# 10_1a.net
KiCad netlist of a schematic drawn in EasyEDA
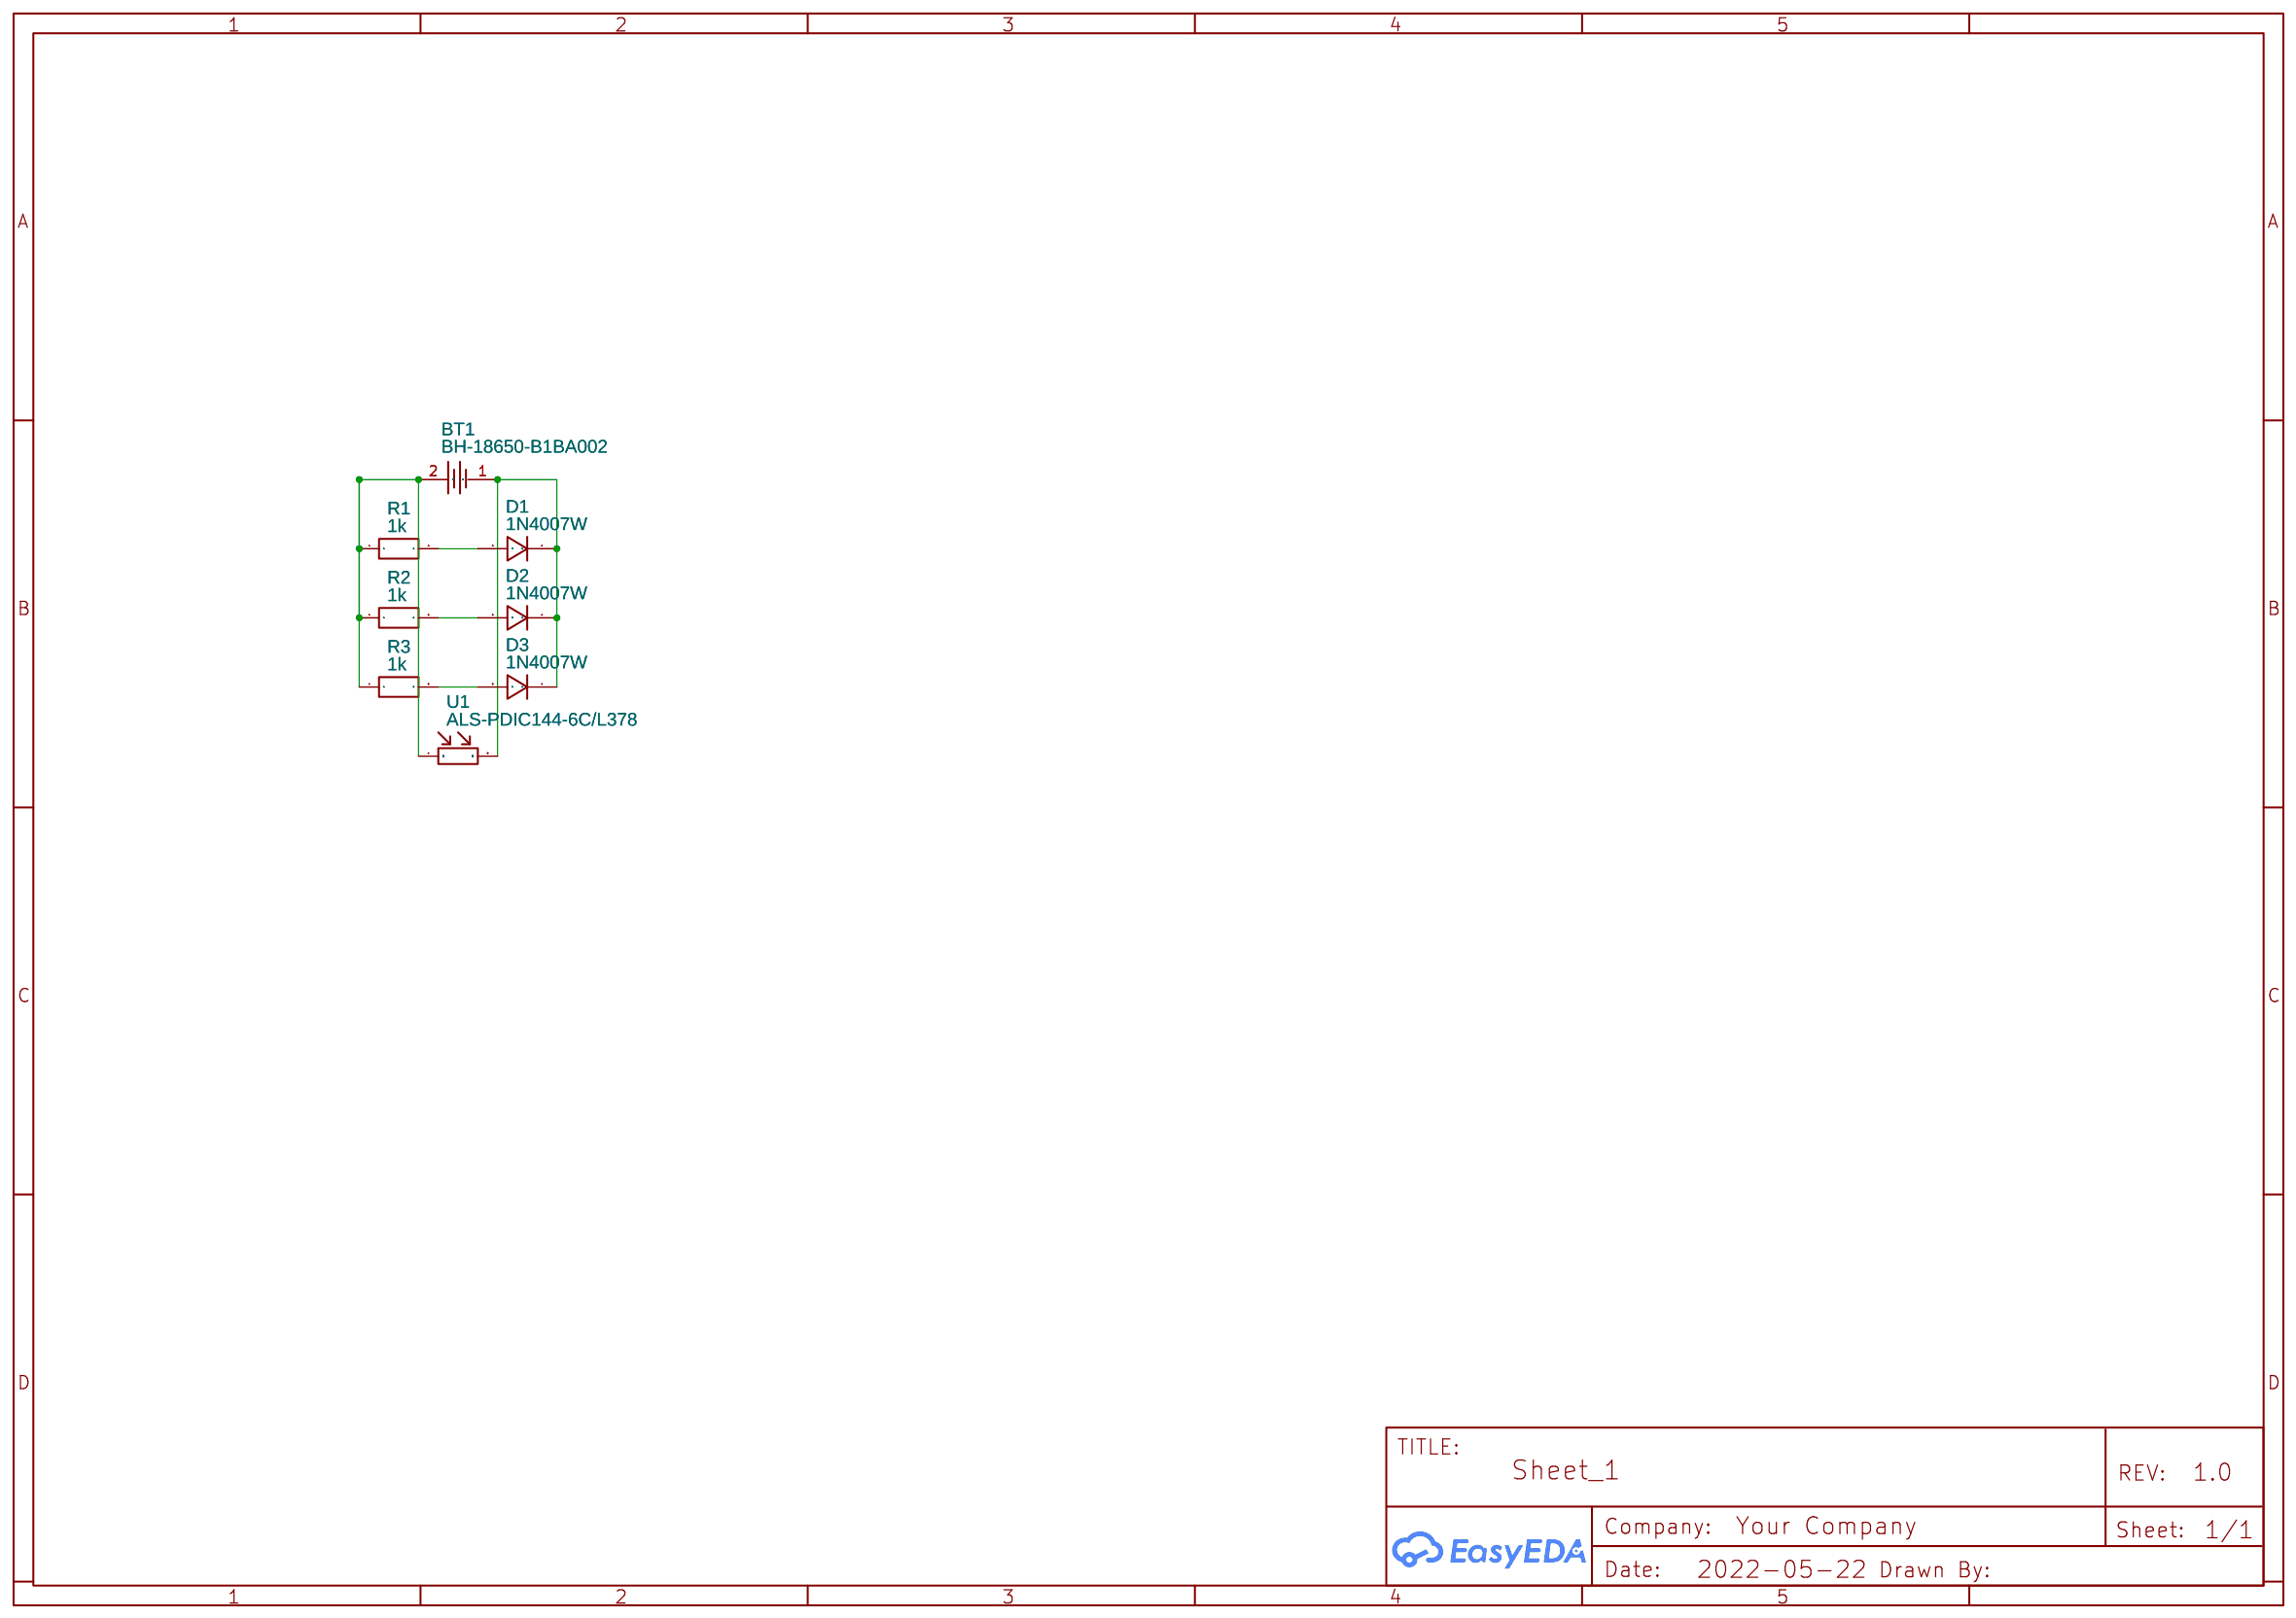
[diagram p0: schematic sheet]

(export (version "E")
  (design (tool "Eeschema 10.0.6"))
  (components
    (comp (ref "BT1")
      (value "BH-18650-B1BA002")
      (fields (field (name "BOM_Supplier Part") "C2988620"))
      (libsource (lib "") (part "BH-18650-B1BA002"))
    )
    (comp (ref "D1")
      (value "1N4007W")
      (fields (field (name "BOM_Supplier Part") "C328592"))
      (libsource (lib "") (part "1N4007W"))
    )
    (comp (ref "D2")
      (value "1N4007W")
      (fields (field (name "BOM_Supplier Part") "C328592"))
      (libsource (lib "") (part "1N4007W"))
    )
    (comp (ref "D3")
      (value "1N4007W")
      (fields (field (name "BOM_Supplier Part") "C328592"))
      (libsource (lib "") (part "1N4007W"))
    )
    (comp (ref "R1") (value "1k") (libsource (lib "") (part "R_0603_EU")))
    (comp (ref "R2") (value "1k") (libsource (lib "") (part "R_0603_EU")))
    (comp (ref "R3") (value "1k") (libsource (lib "") (part "R_0603_EU")))
    (comp (ref "U1")
      (value "ALS-PDIC144-6C/L378")
      (fields (field (name "BOM_Supplier Part") "C2943463"))
      (libsource (lib "") (part "ALS-PDIC144-6C/L378"))
    )
  )
  (nets
    (net (code "1") (name "Net-(D1-Pad2)") (class "Default")
      (node (ref "D1") (pin "2") (pinfunction "2_2") (pintype "unspecified"))
      (node (ref "R1") (pin "2") (pinfunction "2_2") (pintype "unspecified"))
    )
    (net (code "2") (name "Net-(D2-Pad2)") (class "Default")
      (node (ref "D2") (pin "2") (pinfunction "2_2") (pintype "unspecified"))
      (node (ref "R2") (pin "2") (pinfunction "2_2") (pintype "unspecified"))
    )
    (net (code "3") (name "Net-(D3-Pad2)") (class "Default")
      (node (ref "D3") (pin "2") (pinfunction "2_2") (pintype "unspecified"))
      (node (ref "R3") (pin "2") (pinfunction "2_2") (pintype "unspecified"))
    )
    (net (code "4") (name "Net-(U1-VCC)") (class "Default")
      (node (ref "BT1") (pin "2") (pinfunction "2_2") (pintype "input"))
      (node (ref "R1") (pin "1") (pinfunction "1_1") (pintype "unspecified"))
      (node (ref "R2") (pin "1") (pinfunction "1_1") (pintype "unspecified"))
      (node (ref "R3") (pin "1") (pinfunction "1_1") (pintype "unspecified"))
      (node (ref "U1") (pin "1") (pinfunction "VCC_1") (pintype "input"))
    )
    (net (code "5") (name "Net-(U1-VOUT)") (class "Default")
      (node (ref "BT1") (pin "1") (pinfunction "1_1") (pintype "input"))
      (node (ref "D1") (pin "1") (pinfunction "1_1") (pintype "unspecified"))
      (node (ref "D2") (pin "1") (pinfunction "1_1") (pintype "unspecified"))
      (node (ref "D3") (pin "1") (pinfunction "1_1") (pintype "unspecified"))
      (node (ref "U1") (pin "2") (pinfunction "VOUT_2") (pintype "input"))
    )
  )
)
